# 3_USB.net
KiCad netlist of a schematic drawn in Altium Designer
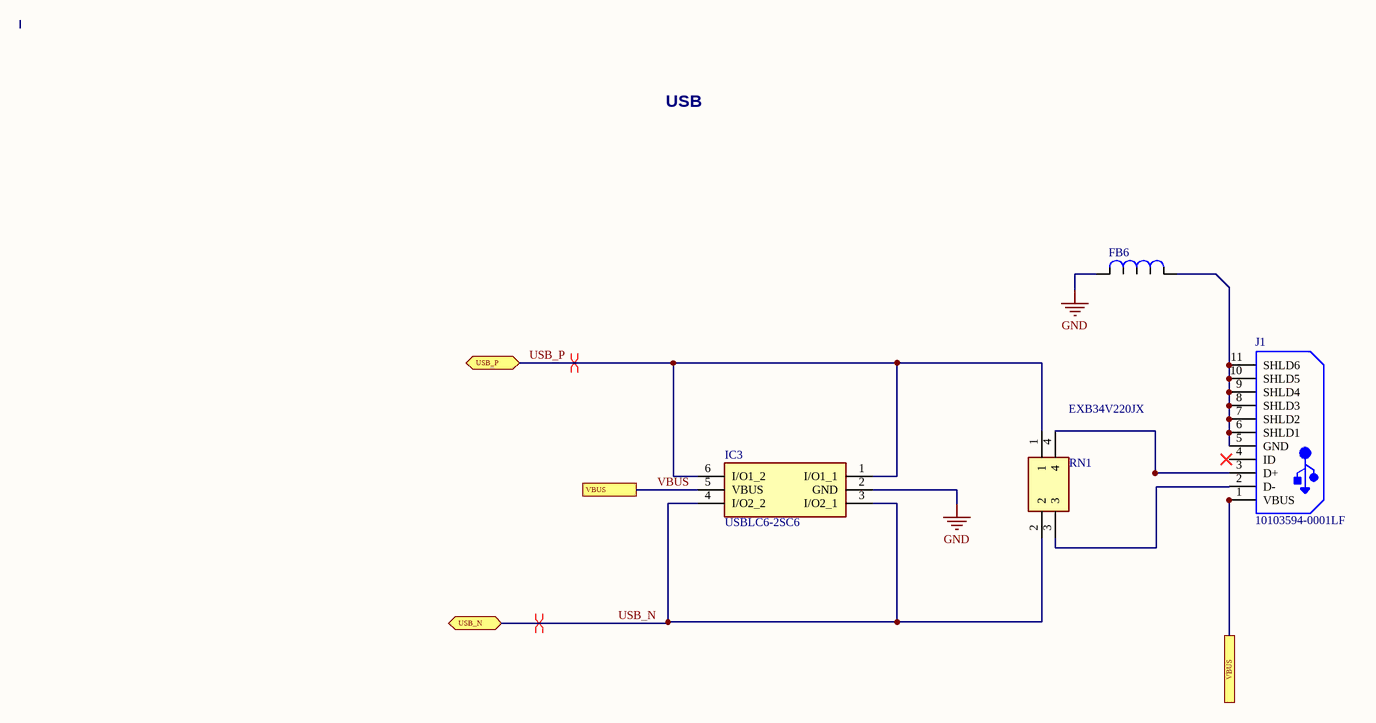
[diagram p0: [3]USB.SchDoc]

(export (version "E")
  (design (tool "Eeschema 10.0.6"))
  (components
    (comp (ref "FB6")
      (value "BLM18AG102SN1D")
      (footprint "Ferrite Bead")
      (description "Ferrite Bead 1KOhm @100MHz")
      (libsource (lib "MasterLib") (part "Ferrite Bead"))
    )
    (comp (ref "IC3")
      (value "USBLC6-2SC6")
      (footprint "SamacSys:SOT95P280X145-6N")
      (description "Integrated Circuit")
      (fields (field (name "MOUSER PART NUMBER") "511-USBLC6-2SC6"))
      (libsource (lib "PCB_Project") (part "USBLC6-2SC6"))
    )
    (comp (ref "J1")
      (value "10103594-0001LF")
      (footprint "FCI-10103594-0001LF_V")
      (description "Micro USB 2.0 B Receptacle, 5 Position, Height 3.24 mm, -55 to 85 degC, RoHS, Tape and Reel")
      (fields (field (name "MANUFACTURER") "FCI Electronics"))
      (libsource (lib "Latium Technologies") (part "USB-5-6SHLD"))
    )
    (comp (ref "RN1")
      (value "EXB34V220JX")
      (footprint "EXB34V103JV")
      (description "Resistor Network")
      (fields (field (name "MANUFACTURER_PART_NUMBER") "EXB34V330JV"))
      (libsource (lib "PCB_High_Voltage_Sensor") (part "EXB34V330JV"))
    )
  )
  (nets
    (net (code "1") (name "/USB_N") (class "Default")
      (node (ref "IC3") (pin "3") (pinfunction "I/O2_1_3") (pintype "passive"))
      (node (ref "IC3") (pin "4") (pinfunction "I/O2_2_4") (pintype "passive"))
      (node (ref "RN1") (pin "2") (pinfunction "2_2") (pintype "passive"))
    )
    (net (code "2") (name "/USB_P") (class "Default")
      (node (ref "IC3") (pin "1") (pinfunction "I/O1_1_1") (pintype "passive"))
      (node (ref "IC3") (pin "6") (pinfunction "I/O1_2_6") (pintype "passive"))
      (node (ref "RN1") (pin "1") (pinfunction "1_1") (pintype "passive"))
    )
    (net (code "3") (name "/VBUS") (class "Default")
      (node (ref "IC3") (pin "5") (pinfunction "VBUS_5") (pintype "passive"))
      (node (ref "J1") (pin "1") (pinfunction "VBUS_1") (pintype "passive"))
    )
    (net (code "4") (name "GND") (class "Default")
      (node (ref "FB6") (pin "2") (pinfunction "2_2") (pintype "passive"))
      (node (ref "IC3") (pin "2") (pinfunction "GND_2") (pintype "passive"))
    )
    (net (code "5") (name "Net-(J1-D+)") (class "Default")
      (node (ref "J1") (pin "3") (pinfunction "D+_3") (pintype "passive"))
      (node (ref "RN1") (pin "4") (pinfunction "4_4") (pintype "passive"))
    )
    (net (code "6") (name "Net-(J1-D-)") (class "Default")
      (node (ref "J1") (pin "2") (pinfunction "D-_2") (pintype "passive"))
      (node (ref "RN1") (pin "3") (pinfunction "3_3") (pintype "passive"))
    )
    (net (code "7") (name "Net-(J1-GND)") (class "Default")
      (node (ref "FB6") (pin "1") (pinfunction "1_1") (pintype "passive"))
      (node (ref "J1") (pin "10") (pinfunction "SHLD5_10") (pintype "passive"))
      (node (ref "J1") (pin "11") (pinfunction "SHLD6_11") (pintype "passive"))
      (node (ref "J1") (pin "5") (pinfunction "GND_5") (pintype "passive"))
      (node (ref "J1") (pin "6") (pinfunction "SHLD1_6") (pintype "passive"))
      (node (ref "J1") (pin "7") (pinfunction "SHLD2_7") (pintype "passive"))
      (node (ref "J1") (pin "8") (pinfunction "SHLD3_8") (pintype "passive"))
      (node (ref "J1") (pin "9") (pinfunction "SHLD4_9") (pintype "passive"))
    )
    (net (code "8") (name "unconnected-(J1-ID-Pad4)") (class "Default")
      (node (ref "J1") (pin "4") (pinfunction "ID_4") (pintype "passive"))
    )
  )
)
